# NANO103.net
KiCad netlist of a schematic drawn in Altium Designer
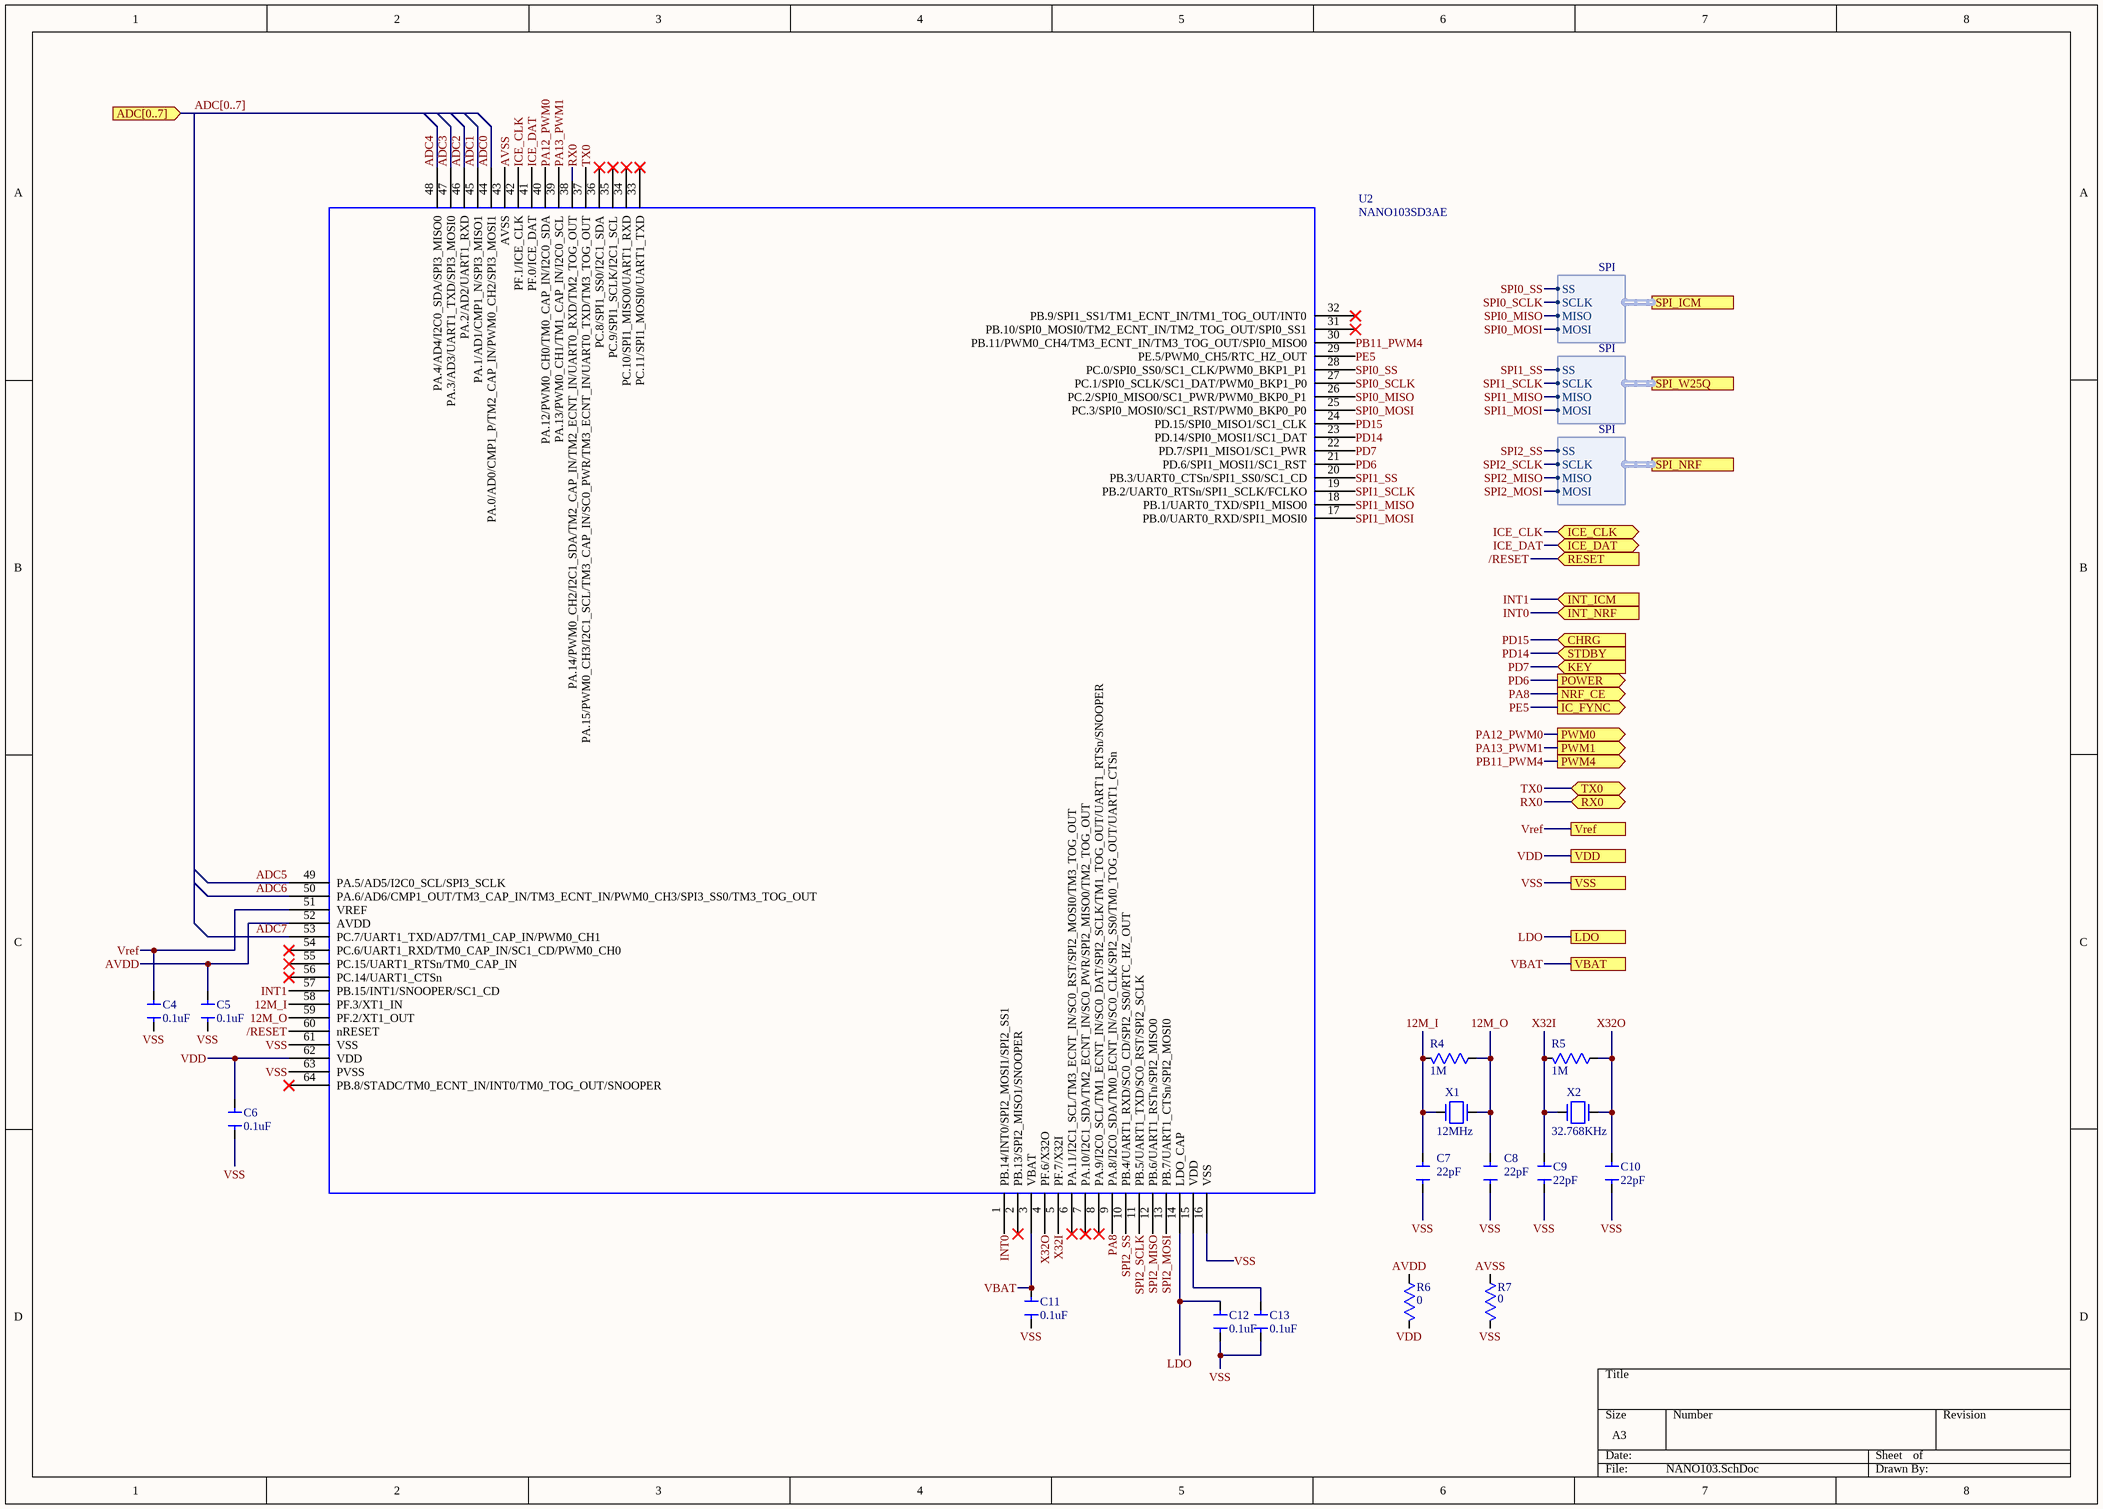
[diagram p0: NANO103.SchDoc]

(export (version "E")
  (design (tool "Eeschema 10.0.6"))
  (components
    (comp (ref "C4")
      (value "0.1uF")
      (footprint "CAP_0402")
      (fields (field (name "Comment") "Cap"))
      (libsource (lib "ZGR") (part "Cap"))
    )
    (comp (ref "C5")
      (value "0.1uF")
      (footprint "CAP_0402")
      (fields (field (name "Comment") "Cap"))
      (libsource (lib "ZGR") (part "Cap"))
    )
    (comp (ref "C6")
      (value "0.1uF")
      (footprint "CAP_0402")
      (fields (field (name "Comment") "Cap"))
      (libsource (lib "ZGR") (part "Cap"))
    )
    (comp (ref "C7")
      (value "22pF")
      (footprint "CAP_0402")
      (fields (field (name "Comment") "Cap"))
      (libsource (lib "ZGR") (part "Cap"))
    )
    (comp (ref "C8")
      (value "22pF")
      (footprint "CAP_0402")
      (fields (field (name "Comment") "Cap"))
      (libsource (lib "ZGR") (part "Cap"))
    )
    (comp (ref "C9")
      (value "22pF")
      (footprint "CAP_0402")
      (fields (field (name "Comment") "Cap"))
      (libsource (lib "ZGR") (part "Cap"))
    )
    (comp (ref "C10")
      (value "22pF")
      (footprint "CAP_0402")
      (fields (field (name "Comment") "Cap"))
      (libsource (lib "ZGR") (part "Cap"))
    )
    (comp (ref "C11")
      (value "0.1uF")
      (footprint "CAP_0402")
      (fields (field (name "Comment") "Cap"))
      (libsource (lib "ZGR") (part "Cap"))
    )
    (comp (ref "C12")
      (value "0.1uF")
      (footprint "CAP_0402")
      (fields (field (name "Comment") "Cap"))
      (libsource (lib "ZGR") (part "Cap"))
    )
    (comp (ref "C13")
      (value "0.1uF")
      (footprint "CAP_0402")
      (fields (field (name "Comment") "Cap"))
      (libsource (lib "ZGR") (part "Cap"))
    )
    (comp (ref "R4")
      (value "1M")
      (footprint "RES_0402")
      (fields (field (name "Comment") "Res"))
      (libsource (lib "ZGR") (part "Res"))
    )
    (comp (ref "R5")
      (value "1M")
      (footprint "RES_0402")
      (fields (field (name "Comment") "Res"))
      (libsource (lib "ZGR") (part "Res"))
    )
    (comp (ref "R6")
      (value "0")
      (footprint "RES_0402")
      (fields (field (name "Comment") "Res"))
      (libsource (lib "ZGR") (part "Res"))
    )
    (comp (ref "R7")
      (value "0")
      (footprint "RES_0402")
      (fields (field (name "Comment") "Res"))
      (libsource (lib "ZGR") (part "Res"))
    )
    (comp (ref "U2")
      (value "NANO103SD3AE")
      (footprint "MCU_LQFP_64_7x7")
      (libsource (lib "NUVOTON") (part "NANO103SD3AE"))
    )
    (comp (ref "X1")
      (value "12MHz")
      (footprint "2520S")
      (fields (field (name "Comment") "Xtal"))
      (libsource (lib "ZGR") (part "Xtal"))
    )
    (comp (ref "X2")
      (value "32.768KHz")
      (footprint "FC-135")
      (fields (field (name "Comment") "Xtal"))
      (libsource (lib "ZGR") (part "Xtal"))
    )
  )
  (nets
    (net (code "2") (name "/12M_I") (class "Default")
      (node (ref "C7") (pin "1") (pinfunction "1_1") (pintype "passive"))
      (node (ref "R4") (pin "1") (pinfunction "1_1") (pintype "passive"))
      (node (ref "U2") (pin "58") (pinfunction "PF.3/XT1_IN_58") (pintype "passive"))
      (node (ref "X1") (pin "2") (pintype "passive"))
    )
    (net (code "3") (name "/12M_O") (class "Default")
      (node (ref "C8") (pin "1") (pinfunction "1_1") (pintype "passive"))
      (node (ref "R4") (pin "2") (pinfunction "2_2") (pintype "passive"))
      (node (ref "U2") (pin "59") (pinfunction "PF.2/XT1_OUT_59") (pintype "passive"))
      (node (ref "X1") (pin "1") (pintype "passive"))
    )
    (net (code "4") (name "/ADC0") (class "Default")
      (node (ref "U2") (pin "44") (pinfunction "PA.0/AD0/CMP1_P/TM2_CAP_IN/PWM0_CH2/SPI3_MOSI1_44") (pintype "passive"))
    )
    (net (code "5") (name "/ADC1") (class "Default")
      (node (ref "U2") (pin "45") (pinfunction "PA.1/AD1/CMP1_N/SPI3_MISO1_45") (pintype "passive"))
    )
    (net (code "6") (name "/ADC2") (class "Default")
      (node (ref "U2") (pin "46") (pinfunction "PA.2/AD2/UART1_RXD_46") (pintype "passive"))
    )
    (net (code "7") (name "/ADC3") (class "Default")
      (node (ref "U2") (pin "47") (pinfunction "PA.3/AD3/UART1_TXD/SPI3_MOSI0_47") (pintype "passive"))
    )
    (net (code "8") (name "/ADC4") (class "Default")
      (node (ref "U2") (pin "48") (pinfunction "PA.4/AD4/I2C0_SDA/SPI3_MISO0_48") (pintype "passive"))
    )
    (net (code "9") (name "/ADC5") (class "Default")
      (node (ref "U2") (pin "49") (pinfunction "PA.5/AD5/I2C0_SCL/SPI3_SCLK_49") (pintype "passive"))
    )
    (net (code "10") (name "/ADC6") (class "Default")
      (node (ref "U2") (pin "50") (pinfunction "PA.6/AD6/CMP1_OUT/TM3_CAP_IN/TM3_ECNT_IN/PWM0_CH3/SPI3_SS0/TM3_TOG_OUT_50") (pintype "passive"))
    )
    (net (code "11") (name "/ADC7") (class "Default")
      (node (ref "U2") (pin "53") (pinfunction "PC.7/UART1_TXD/AD7/TM1_CAP_IN/PWM0_CH1_53") (pintype "passive"))
    )
    (net (code "13") (name "/AVDD") (class "Default")
      (node (ref "C5") (pin "2") (pinfunction "2_2") (pintype "passive"))
      (node (ref "R6") (pin "2") (pinfunction "2_2") (pintype "passive"))
      (node (ref "U2") (pin "52") (pinfunction "AVDD_52") (pintype "passive"))
    )
    (net (code "14") (name "/AVSS") (class "Default")
      (node (ref "R7") (pin "2") (pinfunction "2_2") (pintype "passive"))
      (node (ref "U2") (pin "43") (pinfunction "AVSS_43") (pintype "passive"))
    )
    (net (code "15") (name "/ICE_CLK") (class "Default")
      (node (ref "U2") (pin "42") (pinfunction "PF.1/ICE_CLK_42") (pintype "passive"))
    )
    (net (code "16") (name "/ICE_DAT") (class "Default")
      (node (ref "U2") (pin "41") (pinfunction "PF.0/ICE_DAT_41") (pintype "passive"))
    )
    (net (code "17") (name "/INT0") (class "Default")
      (node (ref "U2") (pin "1") (pinfunction "PB.14/INT0/SPI2_MOSI1/SPI2_SS1_1") (pintype "passive"))
    )
    (net (code "18") (name "/INT1") (class "Default")
      (node (ref "U2") (pin "57") (pinfunction "PB.15/INT1/SNOOPER/SC1_CD_57") (pintype "passive"))
    )
    (net (code "19") (name "/LDO") (class "Default")
      (node (ref "C12") (pin "2") (pinfunction "2_2") (pintype "passive"))
      (node (ref "U2") (pin "14") (pinfunction "LDO_CAP_14") (pintype "passive"))
    )
    (net (code "20") (name "/PA8") (class "Default")
      (node (ref "U2") (pin "9") (pinfunction "PA.8/I2C0_SDA/TM0_ECNT_IN/SC0_CLK/SPI2_SS0/TM0_TOG_OUT/UART1_CTSn_9") (pintype "passive"))
    )
    (net (code "21") (name "/PA12_PWM0") (class "Default")
      (node (ref "U2") (pin "40") (pinfunction "PA.12/PWM0_CH0/TM0_CAP_IN/I2C0_SDA_40") (pintype "passive"))
    )
    (net (code "22") (name "/PA13_PWM1") (class "Default")
      (node (ref "U2") (pin "39") (pinfunction "PA.13/PWM0_CH1/TM1_CAP_IN/I2C0_SCL_39") (pintype "passive"))
    )
    (net (code "23") (name "/PB11_PWM4") (class "Default")
      (node (ref "U2") (pin "30") (pinfunction "PB.11/PWM0_CH4/TM3_ECNT_IN/TM3_TOG_OUT/SPI0_MISO0_30") (pintype "passive"))
    )
    (net (code "24") (name "/PD6") (class "Default")
      (node (ref "U2") (pin "21") (pinfunction "PD.6/SPI1_MOSI1/SC1_RST_21") (pintype "passive"))
    )
    (net (code "25") (name "/PD7") (class "Default")
      (node (ref "U2") (pin "22") (pinfunction "PD.7/SPI1_MISO1/SC1_PWR_22") (pintype "passive"))
    )
    (net (code "26") (name "/PD14") (class "Default")
      (node (ref "U2") (pin "23") (pinfunction "PD.14/SPI0_MOSI1/SC1_DAT_23") (pintype "passive"))
    )
    (net (code "27") (name "/PD15") (class "Default")
      (node (ref "U2") (pin "24") (pinfunction "PD.15/SPI0_MISO1/SC1_CLK_24") (pintype "passive"))
    )
    (net (code "28") (name "/PE5") (class "Default")
      (node (ref "U2") (pin "29") (pinfunction "PE.5/PWM0_CH5/RTC_HZ_OUT_29") (pintype "passive"))
    )
    (net (code "29") (name "/RX0") (class "Default")
      (node (ref "U2") (pin "38") (pinfunction "PA.14/PWM0_CH2/I2C1_SDA/TM2_CAP_IN/TM2_ECNT_IN/UART0_RXD/TM2_TOG_OUT_38") (pintype "passive"))
    )
    (net (code "30") (name "/SPI0_MISO") (class "Default")
      (node (ref "U2") (pin "26") (pinfunction "PC.2/SPI0_MISO0/SC1_PWR/PWM0_BKP0_P1_26") (pintype "passive"))
    )
    (net (code "31") (name "/SPI0_MOSI") (class "Default")
      (node (ref "U2") (pin "25") (pinfunction "PC.3/SPI0_MOSI0/SC1_RST/PWM0_BKP0_P0_25") (pintype "passive"))
    )
    (net (code "32") (name "/SPI0_SCLK") (class "Default")
      (node (ref "U2") (pin "27") (pinfunction "PC.1/SPI0_SCLK/SC1_DAT/PWM0_BKP1_P0_27") (pintype "passive"))
    )
    (net (code "33") (name "/SPI0_SS") (class "Default")
      (node (ref "U2") (pin "28") (pinfunction "PC.0/SPI0_SS0/SC1_CLK/PWM0_BKP1_P1_28") (pintype "passive"))
    )
    (net (code "34") (name "/SPI1_MISO") (class "Default")
      (node (ref "U2") (pin "18") (pinfunction "PB.1/UART0_TXD/SPI1_MISO0_18") (pintype "passive"))
    )
    (net (code "35") (name "/SPI1_MOSI") (class "Default")
      (node (ref "U2") (pin "17") (pinfunction "PB.0/UART0_RXD/SPI1_MOSI0_17") (pintype "passive"))
    )
    (net (code "36") (name "/SPI1_SCLK") (class "Default")
      (node (ref "U2") (pin "19") (pinfunction "PB.2/UART0_RTSn/SPI1_SCLK/FCLKO_19") (pintype "passive"))
    )
    (net (code "37") (name "/SPI1_SS") (class "Default")
      (node (ref "U2") (pin "20") (pinfunction "PB.3/UART0_CTSn/SPI1_SS0/SC1_CD_20") (pintype "passive"))
    )
    (net (code "38") (name "/SPI2_MISO") (class "Default")
      (node (ref "U2") (pin "12") (pinfunction "PB.6/UART1_RSTn/SPI2_MISO0_12") (pintype "passive"))
    )
    (net (code "39") (name "/SPI2_MOSI") (class "Default")
      (node (ref "U2") (pin "13") (pinfunction "PB.7/UART1_CTSn/SPI2_MOSI0_13") (pintype "passive"))
    )
    (net (code "40") (name "/SPI2_SCLK") (class "Default")
      (node (ref "U2") (pin "11") (pinfunction "PB.5/UART1_TXD/SC0_RST/SPI2_SCLK_11") (pintype "passive"))
    )
    (net (code "41") (name "/SPI2_SS") (class "Default")
      (node (ref "U2") (pin "10") (pinfunction "PB.4/UART1_RXD/SC0_CD/SPI2_SS0/RTC_HZ_OUT_10") (pintype "passive"))
    )
    (net (code "42") (name "/TX0") (class "Default")
      (node (ref "U2") (pin "37") (pinfunction "PA.15/PWM0_CH3/I2C1_SCL/TM3_CAP_IN/SC0_PWR/TM3_ECNT_IN/UART0_TXD/TM3_TOG_OUT_37") (pintype "passive"))
    )
    (net (code "43") (name "/VBAT") (class "Default")
      (node (ref "C11") (pin "2") (pinfunction "2_2") (pintype "passive"))
      (node (ref "U2") (pin "3") (pinfunction "VBAT_3") (pintype "passive"))
    )
    (net (code "44") (name "/VDD") (class "Default")
      (node (ref "C6") (pin "2") (pinfunction "2_2") (pintype "passive"))
      (node (ref "R6") (pin "1") (pinfunction "1_1") (pintype "passive"))
      (node (ref "U2") (pin "62") (pinfunction "VDD_62") (pintype "passive"))
    )
    (net (code "45") (name "/VSS") (class "Default")
      (node (ref "C10") (pin "2") (pinfunction "2_2") (pintype "passive"))
      (node (ref "C11") (pin "1") (pinfunction "1_1") (pintype "passive"))
      (node (ref "C12") (pin "1") (pinfunction "1_1") (pintype "passive"))
      (node (ref "C13") (pin "1") (pinfunction "1_1") (pintype "passive"))
      (node (ref "C4") (pin "1") (pinfunction "1_1") (pintype "passive"))
      (node (ref "C5") (pin "1") (pinfunction "1_1") (pintype "passive"))
      (node (ref "C6") (pin "1") (pinfunction "1_1") (pintype "passive"))
      (node (ref "C7") (pin "2") (pinfunction "2_2") (pintype "passive"))
      (node (ref "C8") (pin "2") (pinfunction "2_2") (pintype "passive"))
      (node (ref "C9") (pin "2") (pinfunction "2_2") (pintype "passive"))
      (node (ref "R7") (pin "1") (pinfunction "1_1") (pintype "passive"))
      (node (ref "U2") (pin "16") (pinfunction "VSS_16") (pintype "passive"))
      (node (ref "U2") (pin "61") (pinfunction "VSS_61") (pintype "passive"))
      (node (ref "U2") (pin "63") (pinfunction "PVSS_63") (pintype "passive"))
    )
    (net (code "46") (name "/Vref") (class "Default")
      (node (ref "C4") (pin "2") (pinfunction "2_2") (pintype "passive"))
      (node (ref "U2") (pin "51") (pinfunction "VREF_51") (pintype "passive"))
    )
    (net (code "47") (name "/X32I") (class "Default")
      (node (ref "C9") (pin "1") (pinfunction "1_1") (pintype "passive"))
      (node (ref "R5") (pin "1") (pinfunction "1_1") (pintype "passive"))
      (node (ref "U2") (pin "5") (pinfunction "PF.7/X32I_5") (pintype "passive"))
      (node (ref "X2") (pin "2") (pintype "passive"))
    )
    (net (code "48") (name "/X32O") (class "Default")
      (node (ref "C10") (pin "1") (pinfunction "1_1") (pintype "passive"))
      (node (ref "R5") (pin "2") (pinfunction "2_2") (pintype "passive"))
      (node (ref "U2") (pin "4") (pinfunction "PF.6/X32O_4") (pintype "passive"))
      (node (ref "X2") (pin "1") (pintype "passive"))
    )
    (net (code "50") (name "/{slash}RESET") (class "Default")
      (node (ref "U2") (pin "60") (pinfunction "nRESET_60") (pintype "passive"))
    )
    (net (code "51") (name "Net-(C13-Pad2)") (class "Default")
      (node (ref "C13") (pin "2") (pinfunction "2_2") (pintype "passive"))
      (node (ref "U2") (pin "15") (pinfunction "VDD_15") (pintype "passive"))
    )
    (net (code "52") (name "unconnected-(U2-PA.9{slash}I2C0_SCL{slash}TM1_ECNT_IN{slash}SC0_DAT{slash}SPI2_SCLK{slash}TM1_TOG_OUT{slash}UART1_RTSn{slash}SNOOPER-Pad8)") (class "Default")
      (node (ref "U2") (pin "8") (pinfunction "PA.9/I2C0_SCL/TM1_ECNT_IN/SC0_DAT/SPI2_SCLK/TM1_TOG_OUT/UART1_RTSn/SNOOPER_8") (pintype "passive+no_connect"))
    )
    (net (code "53") (name "unconnected-(U2-PA.10{slash}I2C1_SDA{slash}TM2_ECNT_IN{slash}SC0_PWR{slash}SPI2_MISO0{slash}TM2_TOG_OUT-Pad7)") (class "Default")
      (node (ref "U2") (pin "7") (pinfunction "PA.10/I2C1_SDA/TM2_ECNT_IN/SC0_PWR/SPI2_MISO0/TM2_TOG_OUT_7") (pintype "passive+no_connect"))
    )
    (net (code "54") (name "unconnected-(U2-PA.11{slash}I2C1_SCL{slash}TM3_ECNT_IN{slash}SC0_RST{slash}SPI2_MOSI0{slash}TM3_TOG_OUT-Pad6)") (class "Default")
      (node (ref "U2") (pin "6") (pinfunction "PA.11/I2C1_SCL/TM3_ECNT_IN/SC0_RST/SPI2_MOSI0/TM3_TOG_OUT_6") (pintype "passive+no_connect"))
    )
    (net (code "55") (name "unconnected-(U2-PB.8{slash}STADC{slash}TM0_ECNT_IN{slash}INT0{slash}TM0_TOG_OUT{slash}SNOOPER-Pad64)") (class "Default")
      (node (ref "U2") (pin "64") (pinfunction "PB.8/STADC/TM0_ECNT_IN/INT0/TM0_TOG_OUT/SNOOPER_64") (pintype "passive+no_connect"))
    )
    (net (code "56") (name "unconnected-(U2-PB.9{slash}SPI1_SS1{slash}TM1_ECNT_IN{slash}TM1_TOG_OUT{slash}INT0-Pad32)") (class "Default")
      (node (ref "U2") (pin "32") (pinfunction "PB.9/SPI1_SS1/TM1_ECNT_IN/TM1_TOG_OUT/INT0_32") (pintype "passive+no_connect"))
    )
    (net (code "57") (name "unconnected-(U2-PB.10{slash}SPI0_MOSI0{slash}TM2_ECNT_IN{slash}TM2_TOG_OUT{slash}SPI0_SS1-Pad31)") (class "Default")
      (node (ref "U2") (pin "31") (pinfunction "PB.10/SPI0_MOSI0/TM2_ECNT_IN/TM2_TOG_OUT/SPI0_SS1_31") (pintype "passive+no_connect"))
    )
    (net (code "58") (name "unconnected-(U2-PB.13{slash}SPI2_MISO1{slash}SNOOPER-Pad2)") (class "Default")
      (node (ref "U2") (pin "2") (pinfunction "PB.13/SPI2_MISO1/SNOOPER_2") (pintype "passive+no_connect"))
    )
    (net (code "59") (name "unconnected-(U2-PC.6{slash}UART1_RXD{slash}TM0_CAP_IN{slash}SC1_CD{slash}PWM0_CH0-Pad54)") (class "Default")
      (node (ref "U2") (pin "54") (pinfunction "PC.6/UART1_RXD/TM0_CAP_IN/SC1_CD/PWM0_CH0_54") (pintype "passive+no_connect"))
    )
    (net (code "60") (name "unconnected-(U2-PC.8{slash}SPI1_SS0{slash}I2C1_SDA-Pad36)") (class "Default")
      (node (ref "U2") (pin "36") (pinfunction "PC.8/SPI1_SS0/I2C1_SDA_36") (pintype "passive+no_connect"))
    )
    (net (code "61") (name "unconnected-(U2-PC.9{slash}SPI1_SCLK{slash}I2C1_SCL-Pad35)") (class "Default")
      (node (ref "U2") (pin "35") (pinfunction "PC.9/SPI1_SCLK/I2C1_SCL_35") (pintype "passive+no_connect"))
    )
    (net (code "62") (name "unconnected-(U2-PC.10{slash}SPI1_MISO0{slash}UART1_RXD-Pad34)") (class "Default")
      (node (ref "U2") (pin "34") (pinfunction "PC.10/SPI1_MISO0/UART1_RXD_34") (pintype "passive+no_connect"))
    )
    (net (code "63") (name "unconnected-(U2-PC.11{slash}SPI1_MOSI0{slash}UART1_TXD-Pad33)") (class "Default")
      (node (ref "U2") (pin "33") (pinfunction "PC.11/SPI1_MOSI0/UART1_TXD_33") (pintype "passive+no_connect"))
    )
    (net (code "64") (name "unconnected-(U2-PC.14{slash}UART1_CTSn-Pad56)") (class "Default")
      (node (ref "U2") (pin "56") (pinfunction "PC.14/UART1_CTSn_56") (pintype "passive+no_connect"))
    )
    (net (code "65") (name "unconnected-(U2-PC.15{slash}UART1_RTSn{slash}TM0_CAP_IN-Pad55)") (class "Default")
      (node (ref "U2") (pin "55") (pinfunction "PC.15/UART1_RTSn/TM0_CAP_IN_55") (pintype "passive+no_connect"))
    )
  )
)
